# main.net
KiCad netlist of a schematic drawn in Altium Designer
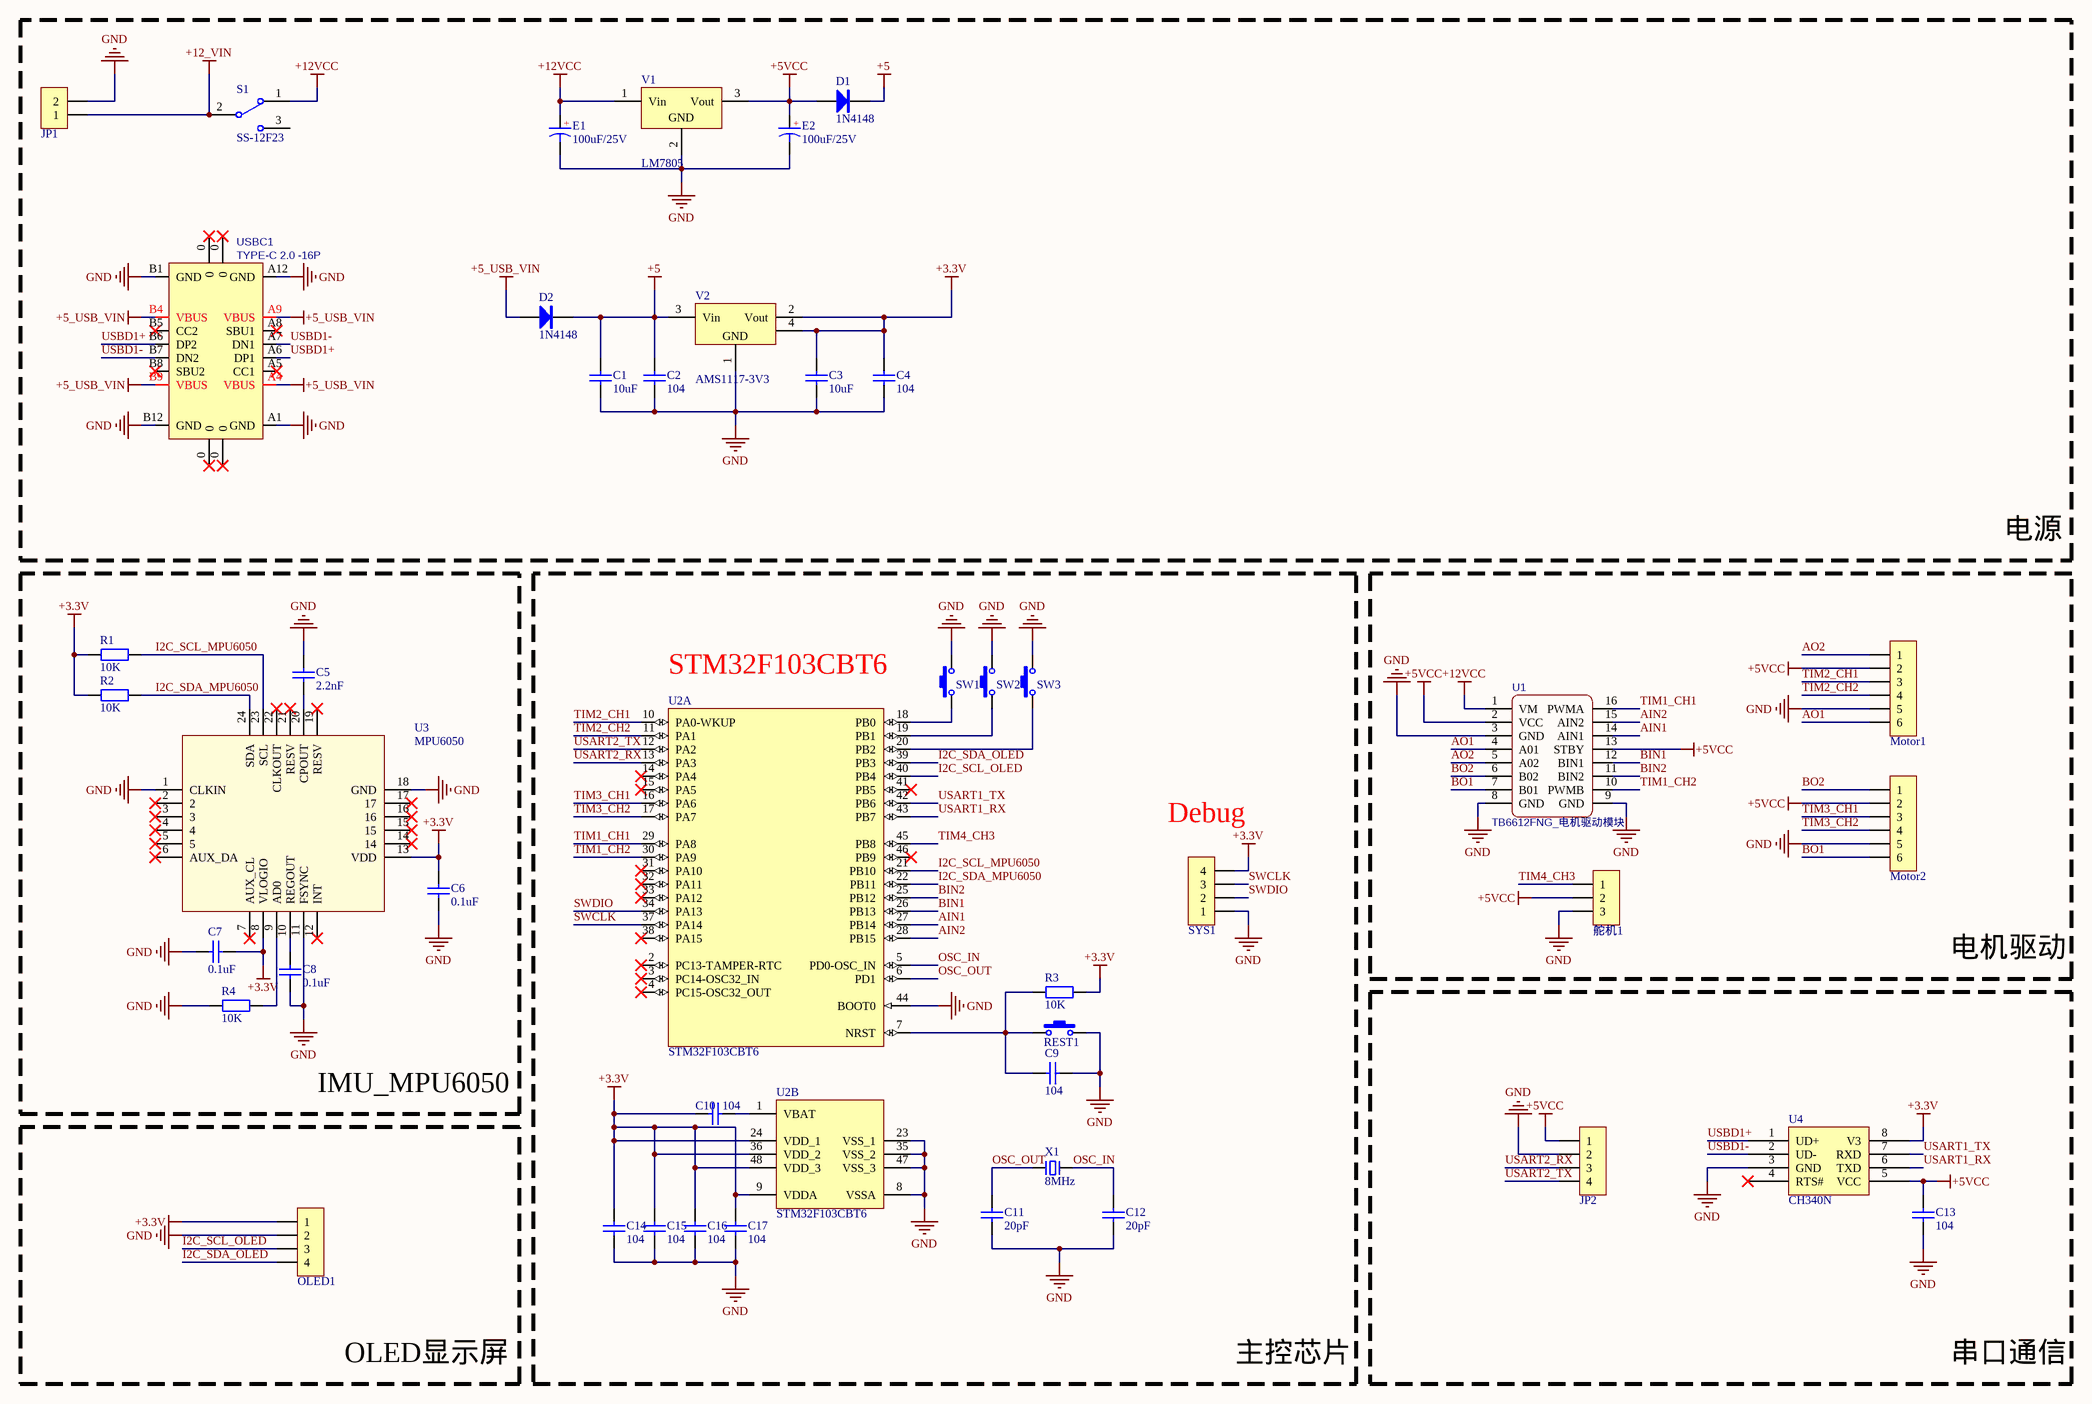
[diagram p0: main.SchDoc]

(export (version "E")
  (design (tool "Eeschema 10.0.6"))
  (components
    (comp (ref "C1")
      (value "10uF")
      (footprint "C0805_L")
      (description "贴片电容/MLCC电容")
      (libsource (lib "0.1 - 电阻-电容-电感-晶振-晶体-磁珠-电位器-法拉电容-馈通电容") (part "C"))
    )
    (comp (ref "C2")
      (value "104")
      (footprint "C0805_L")
      (description "贴片电容/MLCC电容")
      (libsource (lib "0.1 - 电阻-电容-电感-晶振-晶体-磁珠-电位器-法拉电容-馈通电容") (part "C"))
    )
    (comp (ref "C3")
      (value "10uF")
      (footprint "C0805_L")
      (description "贴片电容/MLCC电容")
      (libsource (lib "0.1 - 电阻-电容-电感-晶振-晶体-磁珠-电位器-法拉电容-馈通电容") (part "C"))
    )
    (comp (ref "C4")
      (value "104")
      (footprint "C0805_L")
      (description "贴片电容/MLCC电容")
      (libsource (lib "0.1 - 电阻-电容-电感-晶振-晶体-磁珠-电位器-法拉电容-馈通电容") (part "C"))
    )
    (comp (ref "C5")
      (value "2.2nF")
      (footprint "C0805_L")
      (description "贴片电容/MLCC电容")
      (libsource (lib "0.1 - 电阻-电容-电感-晶振-晶体-磁珠-电位器-法拉电容-馈通电容") (part "C"))
    )
    (comp (ref "C6")
      (value "0.1uF")
      (footprint "C0805_L")
      (description "贴片电容/MLCC电容")
      (libsource (lib "0.1 - 电阻-电容-电感-晶振-晶体-磁珠-电位器-法拉电容-馈通电容") (part "C"))
    )
    (comp (ref "C7")
      (value "0.1uF")
      (footprint "C0805_L")
      (description "贴片电容/MLCC电容")
      (libsource (lib "0.1 - 电阻-电容-电感-晶振-晶体-磁珠-电位器-法拉电容-馈通电容") (part "C"))
    )
    (comp (ref "C8")
      (value "0.1uF")
      (footprint "C0805_L")
      (description "贴片电容/MLCC电容")
      (libsource (lib "0.1 - 电阻-电容-电感-晶振-晶体-磁珠-电位器-法拉电容-馈通电容") (part "C"))
    )
    (comp (ref "C9")
      (value "104")
      (footprint "C0805_L")
      (description "贴片电容/MLCC电容")
      (libsource (lib "0.1 - 电阻-电容-电感-晶振-晶体-磁珠-电位器-法拉电容-馈通电容") (part "C"))
    )
    (comp (ref "C10")
      (value "104")
      (footprint "C0805_L")
      (description "贴片电容/MLCC电容")
      (libsource (lib "0.1 - 电阻-电容-电感-晶振-晶体-磁珠-电位器-法拉电容-馈通电容") (part "C"))
    )
    (comp (ref "C11")
      (value "20pF")
      (footprint "C0805_L")
      (description "贴片电容/MLCC电容")
      (libsource (lib "0.1 - 电阻-电容-电感-晶振-晶体-磁珠-电位器-法拉电容-馈通电容") (part "C"))
    )
    (comp (ref "C12")
      (value "20pF")
      (footprint "C0805_L")
      (description "贴片电容/MLCC电容")
      (libsource (lib "0.1 - 电阻-电容-电感-晶振-晶体-磁珠-电位器-法拉电容-馈通电容") (part "C"))
    )
    (comp (ref "C13")
      (value "104")
      (footprint "C0805_L")
      (description "贴片电容/MLCC电容")
      (libsource (lib "0.1 - 电阻-电容-电感-晶振-晶体-磁珠-电位器-法拉电容-馈通电容") (part "C"))
    )
    (comp (ref "C14")
      (value "104")
      (footprint "C0805_L")
      (description "贴片电容/MLCC电容")
      (libsource (lib "0.1 - 电阻-电容-电感-晶振-晶体-磁珠-电位器-法拉电容-馈通电容") (part "C"))
    )
    (comp (ref "C15")
      (value "104")
      (footprint "C0805_L")
      (description "贴片电容/MLCC电容")
      (libsource (lib "0.1 - 电阻-电容-电感-晶振-晶体-磁珠-电位器-法拉电容-馈通电容") (part "C"))
    )
    (comp (ref "C16")
      (value "104")
      (footprint "C0805_L")
      (description "贴片电容/MLCC电容")
      (libsource (lib "0.1 - 电阻-电容-电感-晶振-晶体-磁珠-电位器-法拉电容-馈通电容") (part "C"))
    )
    (comp (ref "C17")
      (value "104")
      (footprint "C0805_L")
      (description "贴片电容/MLCC电容")
      (libsource (lib "0.1 - 电阻-电容-电感-晶振-晶体-磁珠-电位器-法拉电容-馈通电容") (part "C"))
    )
    (comp (ref "D1")
      (value "1N4148")
      (footprint "MINI_MELF (LL34)")
      (description "开关二极管")
      (libsource (lib "0.2 - 二极管-TVS-ESD-整流桥-放电管") (part "1N4148"))
    )
    (comp (ref "D2")
      (value "1N4148")
      (footprint "MINI_MELF (LL34)")
      (description "开关二极管")
      (libsource (lib "0.2 - 二极管-TVS-ESD-整流桥-放电管") (part "1N4148"))
    )
    (comp (ref "E1")
      (value "100uF/25V")
      (footprint "CE D(6.3*7.7)")
      (description "贴片电解电容")
      (libsource (lib "0.1 - 电阻-电容-电感-晶振-晶体-磁珠-电位器-法拉电容-馈通电容") (part "CE_SMD"))
    )
    (comp (ref "E2")
      (value "100uF/25V")
      (footprint "CE D(6.3*7.7)")
      (description "贴片电解电容")
      (libsource (lib "0.1 - 电阻-电容-电感-晶振-晶体-磁珠-电位器-法拉电容-馈通电容") (part "CE_SMD"))
    )
    (comp (ref "JP1")
      (value "HDR-1X2")
      (footprint "KF350-2P")
      (description "2P接插件")
      (libsource (lib "5.6 - 3.5mm连接器(KF350)") (part "Header 2"))
    )
    (comp (ref "JP2")
      (value "HDR-1X4")
      (footprint "HDR2.54-LI-4P")
      (description "4P接插件")
      (libsource (lib "5.5 - 2.54mm连接器(KF2EDGK_XH2.54_2.54排针排母)") (part "Header 4"))
    )
    (comp (ref "Motor1")
      (value "HDR-1X6")
      (footprint "XH2.54-LI-6P")
      (description "6P接插件")
      (libsource (lib "5.5 - 2.54mm连接器(KF2EDGK_XH2.54_2.54排针排母)") (part "Header 6"))
    )
    (comp (ref "Motor2")
      (value "HDR-1X6")
      (footprint "XH2.54-LI-6P")
      (description "6P接插件")
      (libsource (lib "5.5 - 2.54mm连接器(KF2EDGK_XH2.54_2.54排针排母)") (part "Header 6"))
    )
    (comp (ref "OLED1")
      (value "HDR-1X4")
      (footprint "OLED-IIC-096")
      (description "4P接插件")
      (libsource (lib "5.5 - 2.54mm连接器(KF2EDGK_XH2.54_2.54排针排母)") (part "Header 4"))
    )
    (comp (ref "R1")
      (value "10K")
      (footprint "R0805_L")
      (description "贴片电阻")
      (libsource (lib "0.1 - 电阻-电容-电感-晶振-晶体-磁珠-电位器-法拉电容-馈通电容") (part "R"))
    )
    (comp (ref "R2")
      (value "10K")
      (footprint "R0805_L")
      (description "贴片电阻")
      (libsource (lib "0.1 - 电阻-电容-电感-晶振-晶体-磁珠-电位器-法拉电容-馈通电容") (part "R"))
    )
    (comp (ref "R3")
      (value "10K")
      (footprint "R0805_L")
      (description "贴片电阻")
      (libsource (lib "0.1 - 电阻-电容-电感-晶振-晶体-磁珠-电位器-法拉电容-馈通电容") (part "R"))
    )
    (comp (ref "R4")
      (value "10K")
      (footprint "R0805_L")
      (description "贴片电阻")
      (libsource (lib "0.1 - 电阻-电容-电感-晶振-晶体-磁珠-电位器-法拉电容-馈通电容") (part "R"))
    )
    (comp (ref "REST1")
      (value "3x6x5")
      (footprint "SW SMD-3*6*2.5")
      (description "3x6轻触开关")
      (libsource (lib "0.5 - 按键_开关_蜂鸣器_保险丝_电池_测试点_Mark点_铜柱") (part "SW 3x6"))
    )
    (comp (ref "S1")
      (value "SS-12F23")
      (footprint "SS-12F23")
      (description "1路波动开关")
      (libsource (lib "0.5 - 按键_开关_蜂鸣器_保险丝_电池_测试点_Mark点_铜柱") (part "SSW-1P"))
    )
    (comp (ref "SW1")
      (value "3x6x5")
      (footprint "SW SMD-3*6*2.5")
      (description "微动开关")
      (libsource (lib "0.5 - 按键_开关_蜂鸣器_保险丝_电池_测试点_Mark点_铜柱") (part "SW-PB"))
    )
    (comp (ref "SW2")
      (value "3x6x5")
      (footprint "SW SMD-3*6*2.5")
      (description "微动开关")
      (libsource (lib "0.5 - 按键_开关_蜂鸣器_保险丝_电池_测试点_Mark点_铜柱") (part "SW-PB"))
    )
    (comp (ref "SW3")
      (value "3x6x5")
      (footprint "SW SMD-3*6*2.5")
      (description "微动开关")
      (libsource (lib "0.5 - 按键_开关_蜂鸣器_保险丝_电池_测试点_Mark点_铜柱") (part "SW-PB"))
    )
    (comp (ref "SYS1")
      (value "HDR-1X4")
      (footprint "HDR2.54-LI-4P")
      (description "4P接插件")
      (libsource (lib "") (part "Header 4_1"))
    )
    (comp (ref "U1")
      (value "TB6612FNG_电机驱动模块")
      (footprint "TP6612FNG")
      (fields (field (name "CONTRIBUTOR") "TanAifeng"))
      (libsource (lib "TP6612FNG") (part "TB6612FNG_电机驱动模块"))
    )
    (comp (ref "U2")
      (value "STM32F103CBT6")
      (footprint "STM-LQFP48_N")
      (libsource (lib "2.4 - STM32 F1系列单片机") (part "STM32F103CBT6"))
    )
    (comp (ref "U3")
      (value "MPU6050")
      (footprint "QFN24 4x4_M")
      (description "三轴加速度+三轴陀螺仪")
      (libsource (lib "0.9 - 传感器-存储器-模块") (part "MPU6050"))
    )
    (comp (ref "U4") (value "CH340N") (footprint "SOIC-8") (libsource (lib "CH340N") (part "CH340N")))
    (comp (ref "USBC1")
      (value "TYPE-C 2.0 -16P")
      (footprint "USB-C-SMD_16P")
      (description "USB2.0_Type-C_16Pin母座")
      (libsource (lib "0.6 - 电源_RJ45以太网_音频_SD-TF_SIM_ USB Type-C_HDMI插座") (part "USB2.0_Type-C_16Pin"))
    )
    (comp (ref "V1")
      (value "LM7805")
      (footprint "TO252")
      (description "5V线性稳压芯片")
      (libsource (lib "0.7 - 电源类芯片") (part "7805"))
    )
    (comp (ref "V2")
      (value "AMS1117-3V3")
      (footprint "SOT223_L")
      (description "三端稳压芯片")
      (libsource (lib "0.7 - 电源类芯片") (part "AMS1117"))
    )
    (comp (ref "X1")
      (value "8MHz")
      (footprint "XTAL-5032-2P")
      (description "2脚无源晶振(谐振器）")
      (libsource (lib "0.1 - 电阻-电容-电感-晶振-晶体-磁珠-电位器-法拉电容-馈通电容") (part "XTAL-2P"))
    )
    (comp (ref "舵机1")
      (value "HDR-1X3")
      (footprint "HDR2.54-LI-3P")
      (description "3P接插件")
      (libsource (lib "5.5 - 2.54mm连接器(KF2EDGK_XH2.54_2.54排针排母)") (part "Header 3"))
    )
  )
  (nets
    (net (code "1") (name "+3.3V") (class "Default")
      (node (ref "C10") (pin "1") (pinfunction "1_1") (pintype "passive"))
      (node (ref "C14") (pin "2") (pinfunction "2_2") (pintype "passive"))
      (node (ref "C15") (pin "2") (pinfunction "2_2") (pintype "passive"))
      (node (ref "C16") (pin "2") (pinfunction "2_2") (pintype "passive"))
      (node (ref "C17") (pin "2") (pinfunction "2_2") (pintype "passive"))
      (node (ref "C3") (pin "2") (pinfunction "2_2") (pintype "passive"))
      (node (ref "C4") (pin "2") (pinfunction "2_2") (pintype "passive"))
      (node (ref "C6") (pin "2") (pinfunction "2_2") (pintype "passive"))
      (node (ref "C7") (pin "2") (pinfunction "2_2") (pintype "passive"))
      (node (ref "OLED1") (pin "1") (pinfunction "1_1") (pintype "passive"))
      (node (ref "R1") (pin "2") (pinfunction "2_2") (pintype "passive"))
      (node (ref "R2") (pin "2") (pinfunction "2_2") (pintype "passive"))
      (node (ref "R3") (pin "2") (pinfunction "2_2") (pintype "passive"))
      (node (ref "SYS1") (pin "4") (pinfunction "4_4") (pintype "passive"))
      (node (ref "U2") (pin "24") (pinfunction "VDD_1_24") (pintype "power_in"))
      (node (ref "U2") (pin "36") (pinfunction "VDD_2_36") (pintype "power_in"))
      (node (ref "U2") (pin "48") (pinfunction "VDD_3_48") (pintype "power_in"))
      (node (ref "U2") (pin "9") (pinfunction "VDDA_9") (pintype "power_in"))
      (node (ref "U3") (pin "13") (pinfunction "VDD_13") (pintype "passive"))
      (node (ref "U3") (pin "8") (pinfunction "VLOGIO_8") (pintype "passive"))
      (node (ref "U4") (pin "8") (pinfunction "V3_8") (pintype "passive"))
      (node (ref "V2") (pin "2") (pinfunction "Vout_2") (pintype "passive"))
      (node (ref "V2") (pin "4") (pinfunction "GND_4") (pintype "passive"))
    )
    (net (code "2") (name "+5") (class "Default")
      (node (ref "C1") (pin "2") (pinfunction "2_2") (pintype "passive"))
      (node (ref "C2") (pin "2") (pinfunction "2_2") (pintype "passive"))
      (node (ref "D1") (pin "2") (pinfunction "K_2") (pintype "passive"))
      (node (ref "D2") (pin "2") (pinfunction "K_2") (pintype "passive"))
      (node (ref "V2") (pin "3") (pinfunction "Vin_3") (pintype "passive"))
    )
    (net (code "3") (name "+5VCC") (class "Default")
      (node (ref "C13") (pin "2") (pinfunction "2_2") (pintype "passive"))
      (node (ref "D1") (pin "1") (pinfunction "A_1") (pintype "passive"))
      (node (ref "E2") (pin "1") (pinfunction "1_1") (pintype "passive"))
      (node (ref "JP2") (pin "1") (pinfunction "1_1") (pintype "passive"))
      (node (ref "Motor1") (pin "2") (pinfunction "2_2") (pintype "passive"))
      (node (ref "Motor2") (pin "2") (pinfunction "2_2") (pintype "passive"))
      (node (ref "U1") (pin "13") (pinfunction "STBY_13") (pintype "passive"))
      (node (ref "U1") (pin "2") (pinfunction "VCC_2") (pintype "passive"))
      (node (ref "U4") (pin "5") (pinfunction "VCC_5") (pintype "passive"))
      (node (ref "V1") (pin "3") (pinfunction "Vout_3") (pintype "passive"))
      (node (ref "舵机1") (pin "2") (pinfunction "2_2") (pintype "passive"))
    )
    (net (code "4") (name "+5_USB_VIN") (class "Default")
      (node (ref "D2") (pin "1") (pinfunction "A_1") (pintype "passive"))
      (node (ref "USBC1") (pin "A4") (pinfunction "VBUS_A4") (pintype "passive"))
      (node (ref "USBC1") (pin "A9") (pinfunction "VBUS_A9") (pintype "passive"))
      (node (ref "USBC1") (pin "B4") (pinfunction "VBUS_B4") (pintype "passive"))
      (node (ref "USBC1") (pin "B9") (pinfunction "VBUS_B9") (pintype "passive"))
    )
    (net (code "5") (name "+12VCC") (class "Default")
      (node (ref "E1") (pin "1") (pinfunction "1_1") (pintype "passive"))
      (node (ref "S1") (pin "1") (pinfunction "1_1") (pintype "passive"))
      (node (ref "U1") (pin "1") (pinfunction "VM_1") (pintype "passive"))
      (node (ref "V1") (pin "1") (pinfunction "Vin_1") (pintype "passive"))
    )
    (net (code "6") (name "+12_VIN") (class "Default")
      (node (ref "JP1") (pin "1") (pinfunction "1_1") (pintype "passive"))
      (node (ref "S1") (pin "2") (pinfunction "2_2") (pintype "passive"))
    )
    (net (code "7") (name "/AIN1") (class "Default")
      (node (ref "U1") (pin "14") (pinfunction "AIN1_14") (pintype "passive"))
      (node (ref "U2") (pin "27") (pinfunction "PB14_27") (pintype "bidirectional"))
    )
    (net (code "8") (name "/AIN2") (class "Default")
      (node (ref "U1") (pin "15") (pinfunction "AIN2_15") (pintype "passive"))
      (node (ref "U2") (pin "28") (pinfunction "PB15_28") (pintype "bidirectional"))
    )
    (net (code "9") (name "/AO1") (class "Default")
      (node (ref "Motor1") (pin "6") (pinfunction "6_6") (pintype "passive"))
      (node (ref "U1") (pin "4") (pinfunction "A01_4") (pintype "passive"))
    )
    (net (code "10") (name "/AO2") (class "Default")
      (node (ref "Motor1") (pin "1") (pinfunction "1_1") (pintype "passive"))
      (node (ref "U1") (pin "5") (pinfunction "A02_5") (pintype "passive"))
    )
    (net (code "11") (name "/BIN1") (class "Default")
      (node (ref "U1") (pin "12") (pinfunction "BIN1_12") (pintype "passive"))
      (node (ref "U2") (pin "26") (pinfunction "PB13_26") (pintype "bidirectional"))
    )
    (net (code "12") (name "/BIN2") (class "Default")
      (node (ref "U1") (pin "11") (pinfunction "BIN2_11") (pintype "passive"))
      (node (ref "U2") (pin "25") (pinfunction "PB12_25") (pintype "bidirectional"))
    )
    (net (code "13") (name "/BO1") (class "Default")
      (node (ref "Motor2") (pin "6") (pinfunction "6_6") (pintype "passive"))
      (node (ref "U1") (pin "7") (pinfunction "B01_7") (pintype "passive"))
    )
    (net (code "14") (name "/BO2") (class "Default")
      (node (ref "Motor2") (pin "1") (pinfunction "1_1") (pintype "passive"))
      (node (ref "U1") (pin "6") (pinfunction "B02_6") (pintype "passive"))
    )
    (net (code "15") (name "/I2C_SCL_MPU6050") (class "Default")
      (node (ref "R1") (pin "1") (pinfunction "1_1") (pintype "passive"))
      (node (ref "U2") (pin "21") (pinfunction "PB10_21") (pintype "bidirectional"))
      (node (ref "U3") (pin "23") (pinfunction "SCL_23") (pintype "passive"))
    )
    (net (code "16") (name "/I2C_SCL_OLED") (class "Default")
      (node (ref "OLED1") (pin "3") (pinfunction "3_3") (pintype "passive"))
      (node (ref "U2") (pin "40") (pinfunction "PB4_40") (pintype "bidirectional"))
    )
    (net (code "17") (name "/I2C_SDA_MPU6050") (class "Default")
      (node (ref "R2") (pin "1") (pinfunction "1_1") (pintype "passive"))
      (node (ref "U2") (pin "22") (pinfunction "PB11_22") (pintype "bidirectional"))
      (node (ref "U3") (pin "24") (pinfunction "SDA_24") (pintype "passive"))
    )
    (net (code "18") (name "/I2C_SDA_OLED") (class "Default")
      (node (ref "OLED1") (pin "4") (pinfunction "4_4") (pintype "passive"))
      (node (ref "U2") (pin "39") (pinfunction "PB3_39") (pintype "bidirectional"))
    )
    (net (code "19") (name "/OSC_IN") (class "Default")
      (node (ref "C12") (pin "2") (pinfunction "2_2") (pintype "passive"))
      (node (ref "U2") (pin "5") (pinfunction "PD0-OSC_IN_5") (pintype "bidirectional"))
      (node (ref "X1") (pin "2") (pinfunction "2_2") (pintype "passive"))
    )
    (net (code "20") (name "/OSC_OUT") (class "Default")
      (node (ref "C11") (pin "2") (pinfunction "2_2") (pintype "passive"))
      (node (ref "U2") (pin "6") (pinfunction "PD1_6") (pintype "bidirectional"))
      (node (ref "X1") (pin "1") (pinfunction "1_1") (pintype "passive"))
    )
    (net (code "21") (name "/SWCLK") (class "Default")
      (node (ref "SYS1") (pin "3") (pinfunction "3_3") (pintype "passive"))
      (node (ref "U2") (pin "37") (pinfunction "PA14_37") (pintype "bidirectional"))
    )
    (net (code "22") (name "/SWDIO") (class "Default")
      (node (ref "SYS1") (pin "2") (pinfunction "2_2") (pintype "passive"))
      (node (ref "U2") (pin "34") (pinfunction "PA13_34") (pintype "bidirectional"))
    )
    (net (code "23") (name "/TIM1_CH1") (class "Default")
      (node (ref "U1") (pin "16") (pinfunction "PWMA_16") (pintype "passive"))
      (node (ref "U2") (pin "29") (pinfunction "PA8_29") (pintype "bidirectional"))
    )
    (net (code "24") (name "/TIM1_CH2") (class "Default")
      (node (ref "U1") (pin "10") (pinfunction "PWMB_10") (pintype "passive"))
      (node (ref "U2") (pin "30") (pinfunction "PA9_30") (pintype "bidirectional"))
    )
    (net (code "25") (name "/TIM2_CH1") (class "Default")
      (node (ref "Motor1") (pin "3") (pinfunction "3_3") (pintype "passive"))
      (node (ref "U2") (pin "10") (pinfunction "PA0-WKUP_10") (pintype "bidirectional"))
    )
    (net (code "26") (name "/TIM2_CH2") (class "Default")
      (node (ref "Motor1") (pin "4") (pinfunction "4_4") (pintype "passive"))
      (node (ref "U2") (pin "11") (pinfunction "PA1_11") (pintype "bidirectional"))
    )
    (net (code "27") (name "/TIM3_CH1") (class "Default")
      (node (ref "Motor2") (pin "3") (pinfunction "3_3") (pintype "passive"))
      (node (ref "U2") (pin "16") (pinfunction "PA6_16") (pintype "bidirectional"))
    )
    (net (code "28") (name "/TIM3_CH2") (class "Default")
      (node (ref "Motor2") (pin "4") (pinfunction "4_4") (pintype "passive"))
      (node (ref "U2") (pin "17") (pinfunction "PA7_17") (pintype "bidirectional"))
    )
    (net (code "29") (name "/TIM4_CH3") (class "Default")
      (node (ref "U2") (pin "45") (pinfunction "PB8_45") (pintype "bidirectional"))
      (node (ref "舵机1") (pin "1") (pinfunction "1_1") (pintype "passive"))
    )
    (net (code "30") (name "/USART1_RX") (class "Default")
      (node (ref "U2") (pin "43") (pinfunction "PB7_43") (pintype "bidirectional"))
      (node (ref "U4") (pin "6") (pinfunction "TXD_6") (pintype "passive"))
    )
    (net (code "31") (name "/USART1_TX") (class "Default")
      (node (ref "U2") (pin "42") (pinfunction "PB6_42") (pintype "bidirectional"))
      (node (ref "U4") (pin "7") (pinfunction "RXD_7") (pintype "passive"))
    )
    (net (code "32") (name "/USART2_RX") (class "Default")
      (node (ref "JP2") (pin "3") (pinfunction "3_3") (pintype "passive"))
      (node (ref "U2") (pin "13") (pinfunction "PA3_13") (pintype "bidirectional"))
    )
    (net (code "33") (name "/USART2_TX") (class "Default")
      (node (ref "JP2") (pin "4") (pinfunction "4_4") (pintype "passive"))
      (node (ref "U2") (pin "12") (pinfunction "PA2_12") (pintype "bidirectional"))
    )
    (net (code "34") (name "/USBD1+") (class "Default")
      (node (ref "U4") (pin "1") (pinfunction "UD+_1") (pintype "passive"))
      (node (ref "USBC1") (pin "A6") (pinfunction "DP1_A6") (pintype "passive"))
      (node (ref "USBC1") (pin "B6") (pinfunction "DP2_B6") (pintype "passive"))
    )
    (net (code "35") (name "/USBD1-") (class "Default")
      (node (ref "U4") (pin "2") (pinfunction "UD-_2") (pintype "passive"))
      (node (ref "USBC1") (pin "A7") (pinfunction "DN1_A7") (pintype "passive"))
      (node (ref "USBC1") (pin "B7") (pinfunction "DN2_B7") (pintype "passive"))
    )
    (net (code "36") (name "GND") (class "Default")
      (node (ref "C1") (pin "1") (pinfunction "1_1") (pintype "passive"))
      (node (ref "C11") (pin "1") (pinfunction "1_1") (pintype "passive"))
      (node (ref "C12") (pin "1") (pinfunction "1_1") (pintype "passive"))
      (node (ref "C13") (pin "1") (pinfunction "1_1") (pintype "passive"))
      (node (ref "C14") (pin "1") (pinfunction "1_1") (pintype "passive"))
      (node (ref "C15") (pin "1") (pinfunction "1_1") (pintype "passive"))
      (node (ref "C16") (pin "1") (pinfunction "1_1") (pintype "passive"))
      (node (ref "C17") (pin "1") (pinfunction "1_1") (pintype "passive"))
      (node (ref "C2") (pin "1") (pinfunction "1_1") (pintype "passive"))
      (node (ref "C3") (pin "1") (pinfunction "1_1") (pintype "passive"))
      (node (ref "C4") (pin "1") (pinfunction "1_1") (pintype "passive"))
      (node (ref "C5") (pin "2") (pinfunction "2_2") (pintype "passive"))
      (node (ref "C6") (pin "1") (pinfunction "1_1") (pintype "passive"))
      (node (ref "C7") (pin "1") (pinfunction "1_1") (pintype "passive"))
      (node (ref "C8") (pin "1") (pinfunction "1_1") (pintype "passive"))
      (node (ref "C9") (pin "2") (pinfunction "2_2") (pintype "passive"))
      (node (ref "E1") (pin "2") (pinfunction "2_2") (pintype "passive"))
      (node (ref "E2") (pin "2") (pinfunction "2_2") (pintype "passive"))
      (node (ref "JP1") (pin "2") (pinfunction "2_2") (pintype "passive"))
      (node (ref "JP2") (pin "2") (pinfunction "2_2") (pintype "passive"))
      (node (ref "Motor1") (pin "5") (pinfunction "5_5") (pintype "passive"))
      (node (ref "Motor2") (pin "5") (pinfunction "5_5") (pintype "passive"))
      (node (ref "OLED1") (pin "2") (pinfunction "2_2") (pintype "passive"))
      (node (ref "R4") (pin "1") (pinfunction "1_1") (pintype "passive"))
      (node (ref "REST1") (pin "2") (pinfunction "2_2") (pintype "passive"))
      (node (ref "SW1") (pin "2") (pinfunction "2_2") (pintype "passive"))
      (node (ref "SW2") (pin "2") (pinfunction "2_2") (pintype "passive"))
      (node (ref "SW3") (pin "2") (pinfunction "2_2") (pintype "passive"))
      (node (ref "SYS1") (pin "1") (pinfunction "1_1") (pintype "passive"))
      (node (ref "U1") (pin "3") (pinfunction "GND_3") (pintype "passive"))
      (node (ref "U1") (pin "8") (pinfunction "GND_8") (pintype "passive"))
      (node (ref "U1") (pin "9") (pinfunction "GND_9") (pintype "passive"))
      (node (ref "U2") (pin "23") (pinfunction "VSS_1_23") (pintype "power_in"))
      (node (ref "U2") (pin "35") (pinfunction "VSS_2_35") (pintype "power_in"))
      (node (ref "U2") (pin "44") (pinfunction "BOOT0_44") (pintype "input"))
      (node (ref "U2") (pin "47") (pinfunction "VSS_3_47") (pintype "power_in"))
      (node (ref "U2") (pin "8") (pinfunction "VSSA_8") (pintype "power_in"))
      (node (ref "U3") (pin "1") (pinfunction "CLKIN_1") (pintype "passive"))
      (node (ref "U3") (pin "11") (pinfunction "FSYNC_11") (pintype "passive"))
      (node (ref "U3") (pin "18") (pinfunction "GND_18") (pintype "passive"))
      (node (ref "U4") (pin "3") (pinfunction "GND_3") (pintype "passive"))
      (node (ref "USBC1") (pin "A1") (pinfunction "GND_A1") (pintype "passive"))
      (node (ref "USBC1") (pin "A12") (pinfunction "GND_A12") (pintype "passive"))
      (node (ref "USBC1") (pin "B1") (pinfunction "GND_B1") (pintype "passive"))
      (node (ref "USBC1") (pin "B12") (pinfunction "GND_B12") (pintype "passive"))
      (node (ref "V1") (pin "2") (pinfunction "GND_2") (pintype "passive"))
      (node (ref "V2") (pin "1") (pinfunction "GND_1") (pintype "passive"))
      (node (ref "舵机1") (pin "3") (pinfunction "3_3") (pintype "passive"))
    )
    (net (code "37") (name "Net-(U2A-NRST)") (class "Default")
      (node (ref "C9") (pin "1") (pinfunction "1_1") (pintype "passive"))
      (node (ref "R3") (pin "1") (pinfunction "1_1") (pintype "passive"))
      (node (ref "REST1") (pin "1") (pinfunction "1_1") (pintype "passive"))
      (node (ref "U2") (pin "7") (pinfunction "NRST_7") (pintype "bidirectional"))
    )
    (net (code "38") (name "Net-(U2A-PB0)") (class "Default")
      (node (ref "SW1") (pin "1") (pinfunction "1_1") (pintype "passive"))
      (node (ref "U2") (pin "18") (pinfunction "PB0_18") (pintype "bidirectional"))
    )
    (net (code "39") (name "Net-(U2A-PB1)") (class "Default")
      (node (ref "SW2") (pin "1") (pinfunction "1_1") (pintype "passive"))
      (node (ref "U2") (pin "19") (pinfunction "PB1_19") (pintype "bidirectional"))
    )
    (net (code "40") (name "Net-(U2A-PB2)") (class "Default")
      (node (ref "SW3") (pin "1") (pinfunction "1_1") (pintype "passive"))
      (node (ref "U2") (pin "20") (pinfunction "PB2_20") (pintype "bidirectional"))
    )
    (net (code "41") (name "Net-(U2B-VBAT)") (class "Default")
      (node (ref "C10") (pin "2") (pinfunction "2_2") (pintype "passive"))
      (node (ref "U2") (pin "1") (pinfunction "VBAT_1") (pintype "power_in"))
    )
    (net (code "42") (name "Net-(U3-AD0)") (class "Default")
      (node (ref "R4") (pin "2") (pinfunction "2_2") (pintype "passive"))
      (node (ref "U3") (pin "9") (pinfunction "AD0_9") (pintype "passive"))
    )
    (net (code "43") (name "Net-(U3-CPOUT)") (class "Default")
      (node (ref "C5") (pin "1") (pinfunction "1_1") (pintype "passive"))
      (node (ref "U3") (pin "20") (pinfunction "CPOUT_20") (pintype "passive"))
    )
    (net (code "44") (name "Net-(U3-REGOUT)") (class "Default")
      (node (ref "C8") (pin "2") (pinfunction "2_2") (pintype "passive"))
      (node (ref "U3") (pin "10") (pinfunction "REGOUT_10") (pintype "passive"))
    )
    (net (code "45") (name "unconnected-(S1-Pad3)") (class "Default")
      (node (ref "S1") (pin "3") (pinfunction "3_3") (pintype "passive"))
    )
    (net (code "46") (name "unconnected-(U2A-PA4-Pad14)") (class "Default")
      (node (ref "U2") (pin "14") (pinfunction "PA4_14") (pintype "bidirectional+no_connect"))
    )
    (net (code "47") (name "unconnected-(U2A-PA5-Pad15)") (class "Default")
      (node (ref "U2") (pin "15") (pinfunction "PA5_15") (pintype "bidirectional+no_connect"))
    )
    (net (code "48") (name "unconnected-(U2A-PA10-Pad31)") (class "Default")
      (node (ref "U2") (pin "31") (pinfunction "PA10_31") (pintype "bidirectional+no_connect"))
    )
    (net (code "49") (name "unconnected-(U2A-PA11-Pad32)") (class "Default")
      (node (ref "U2") (pin "32") (pinfunction "PA11_32") (pintype "bidirectional+no_connect"))
    )
    (net (code "50") (name "unconnected-(U2A-PA12-Pad33)") (class "Default")
      (node (ref "U2") (pin "33") (pinfunction "PA12_33") (pintype "bidirectional+no_connect"))
    )
    (net (code "51") (name "unconnected-(U2A-PA15-Pad38)") (class "Default")
      (node (ref "U2") (pin "38") (pinfunction "PA15_38") (pintype "bidirectional+no_connect"))
    )
    (net (code "52") (name "unconnected-(U2A-PB5-Pad41)") (class "Default")
      (node (ref "U2") (pin "41") (pinfunction "PB5_41") (pintype "bidirectional+no_connect"))
    )
    (net (code "53") (name "unconnected-(U2A-PB9-Pad46)") (class "Default")
      (node (ref "U2") (pin "46") (pinfunction "PB9_46") (pintype "bidirectional+no_connect"))
    )
    (net (code "54") (name "unconnected-(U2A-PC13-TAMPER-RTC-Pad2)") (class "Default")
      (node (ref "U2") (pin "2") (pinfunction "PC13-TAMPER-RTC_2") (pintype "bidirectional+no_connect"))
    )
    (net (code "55") (name "unconnected-(U2A-PC14-OSC32_IN-Pad3)") (class "Default")
      (node (ref "U2") (pin "3") (pinfunction "PC14-OSC32_IN_3") (pintype "bidirectional+no_connect"))
    )
    (net (code "56") (name "unconnected-(U2A-PC15-OSC32_OUT-Pad4)") (class "Default")
      (node (ref "U2") (pin "4") (pinfunction "PC15-OSC32_OUT_4") (pintype "bidirectional+no_connect"))
    )
    (net (code "57") (name "unconnected-(U3-AUX_CL-Pad7)") (class "Default")
      (node (ref "U3") (pin "7") (pinfunction "AUX_CL_7") (pintype "passive+no_connect"))
    )
    (net (code "58") (name "unconnected-(U3-AUX_DA-Pad6)") (class "Default")
      (node (ref "U3") (pin "6") (pinfunction "AUX_DA_6") (pintype "passive+no_connect"))
    )
    (net (code "59") (name "unconnected-(U3-CLKOUT-Pad22)") (class "Default")
      (node (ref "U3") (pin "22") (pinfunction "CLKOUT_22") (pintype "passive+no_connect"))
    )
    (net (code "60") (name "unconnected-(U3-INT-Pad12)") (class "Default")
      (node (ref "U3") (pin "12") (pinfunction "INT_12") (pintype "passive+no_connect"))
    )
    (net (code "61") (name "unconnected-(U3-Pad2)") (class "Default")
      (node (ref "U3") (pin "2") (pinfunction "2_2") (pintype "passive+no_connect"))
    )
    (net (code "62") (name "unconnected-(U3-Pad3)") (class "Default")
      (node (ref "U3") (pin "3") (pinfunction "3_3") (pintype "passive+no_connect"))
    )
    (net (code "63") (name "unconnected-(U3-Pad4)") (class "Default")
      (node (ref "U3") (pin "4") (pinfunction "4_4") (pintype "passive+no_connect"))
    )
    (net (code "64") (name "unconnected-(U3-Pad5)") (class "Default")
      (node (ref "U3") (pin "5") (pinfunction "5_5") (pintype "passive+no_connect"))
    )
    (net (code "65") (name "unconnected-(U3-Pad14)") (class "Default")
      (node (ref "U3") (pin "14") (pinfunction "14_14") (pintype "passive+no_connect"))
    )
    (net (code "66") (name "unconnected-(U3-Pad15)") (class "Default")
      (node (ref "U3") (pin "15") (pinfunction "15_15") (pintype "passive+no_connect"))
    )
    (net (code "67") (name "unconnected-(U3-Pad16)") (class "Default")
      (node (ref "U3") (pin "16") (pinfunction "16_16") (pintype "passive+no_connect"))
    )
    (net (code "68") (name "unconnected-(U3-Pad17)") (class "Default")
      (node (ref "U3") (pin "17") (pinfunction "17_17") (pintype "passive+no_connect"))
    )
    (net (code "69") (name "unconnected-(U3-RESV-Pad19)") (class "Default")
      (node (ref "U3") (pin "19") (pinfunction "RESV_19") (pintype "passive+no_connect"))
    )
    (net (code "70") (name "unconnected-(U3-RESV-Pad21)") (class "Default")
      (node (ref "U3") (pin "21") (pinfunction "RESV_21") (pintype "passive+no_connect"))
    )
    (net (code "71") (name "unconnected-(U4-RTS#-Pad4)") (class "Default")
      (node (ref "U4") (pin "4") (pinfunction "RTS#_4") (pintype "passive+no_connect"))
    )
    (net (code "72") (name "unconnected-(USBC1-CC1-PadA5)") (class "Default")
      (node (ref "USBC1") (pin "A5") (pinfunction "CC1_A5") (pintype "passive+no_connect"))
    )
    (net (code "73") (name "unconnected-(USBC1-CC2-PadB5)") (class "Default")
      (node (ref "USBC1") (pin "B5") (pinfunction "CC2_B5") (pintype "passive+no_connect"))
    )
    (net (code "74") (name "unconnected-(USBC1-Pad0)") (class "Default")
      (node (ref "USBC1") (pin "0") (pinfunction "0_0") (pintype "passive+no_connect"))
    )
    (net (code "75") (name "unconnected-(USBC1-Pad0)_1") (class "Default")
      (node (ref "USBC1") (pin "0") (pinfunction "0_0") (pintype "passive+no_connect"))
    )
    (net (code "76") (name "unconnected-(USBC1-Pad0)_2") (class "Default")
      (node (ref "USBC1") (pin "0") (pinfunction "0_0") (pintype "passive+no_connect"))
    )
    (net (code "77") (name "unconnected-(USBC1-Pad0)_3") (class "Default")
      (node (ref "USBC1") (pin "0") (pinfunction "0_0") (pintype "passive+no_connect"))
    )
    (net (code "78") (name "unconnected-(USBC1-SBU1-PadA8)") (class "Default")
      (node (ref "USBC1") (pin "A8") (pinfunction "SBU1_A8") (pintype "passive+no_connect"))
    )
    (net (code "79") (name "unconnected-(USBC1-SBU2-PadB8)") (class "Default")
      (node (ref "USBC1") (pin "B8") (pinfunction "SBU2_B8") (pintype "passive+no_connect"))
    )
  )
)
